# 1-Schematic_charger.net
KiCad netlist of a schematic drawn in EasyEDA
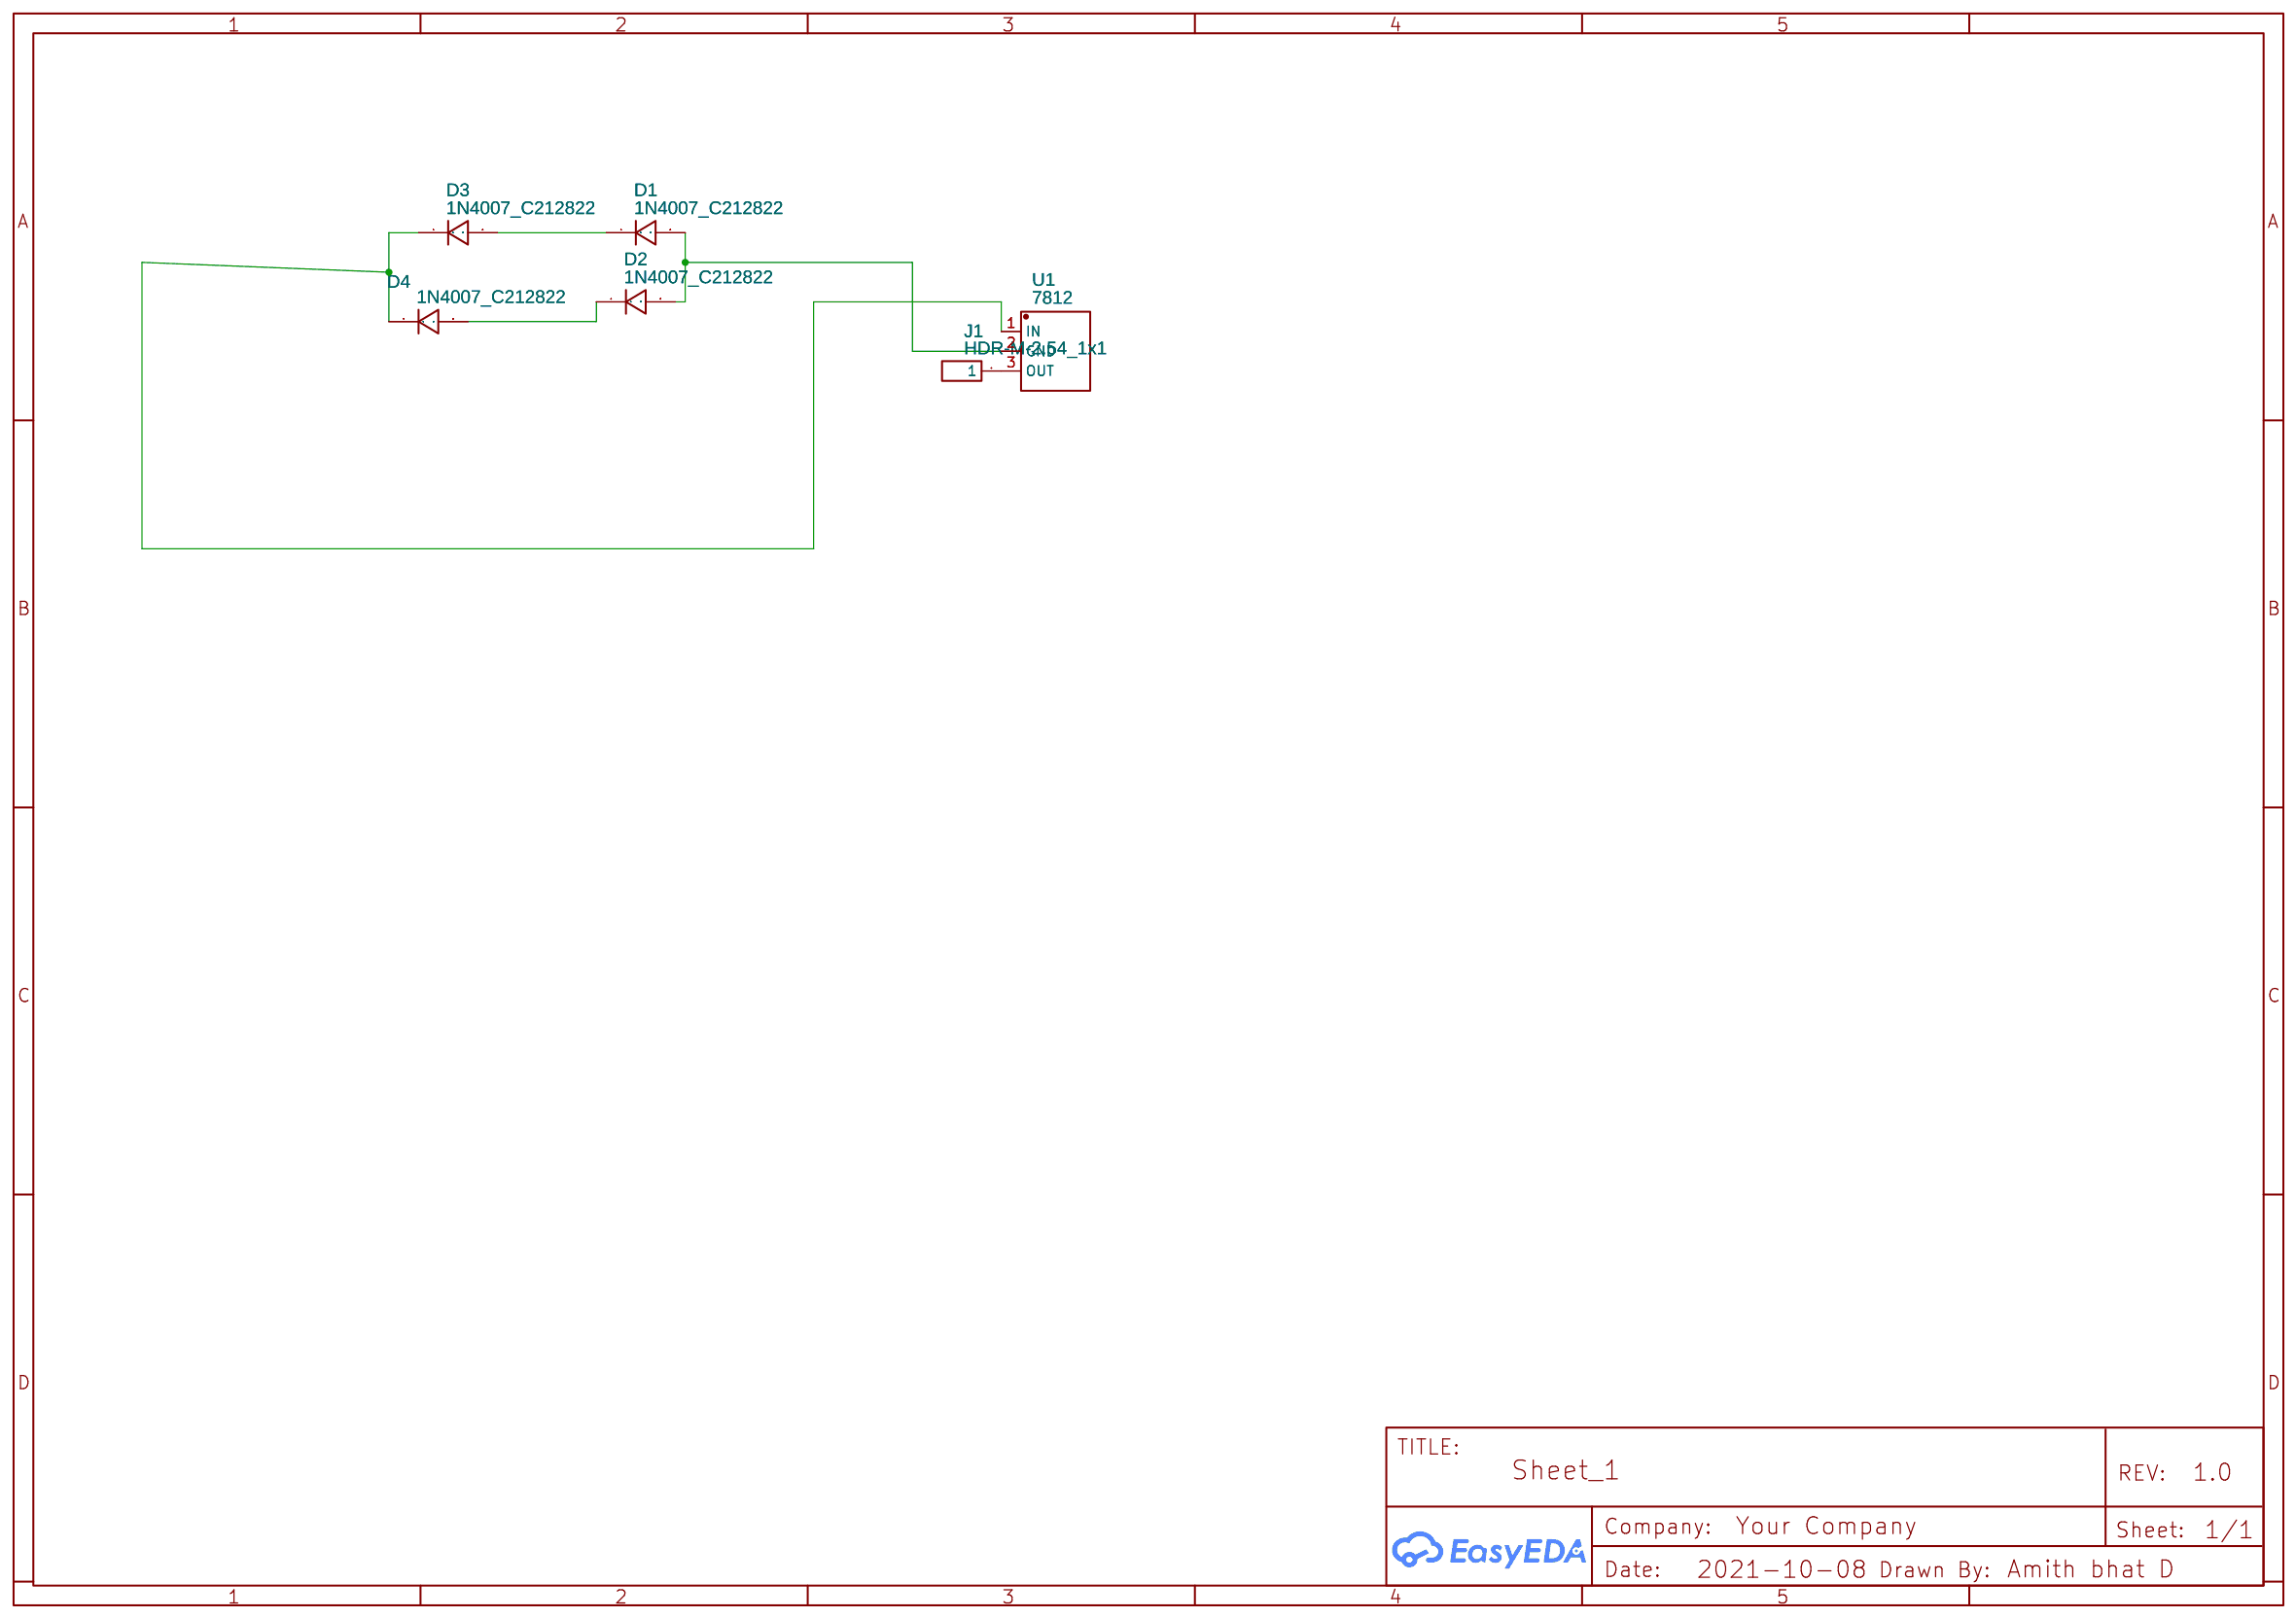
[diagram p0: schematic sheet]

(export (version "E")
  (design (tool "Eeschema 10.0.6"))
  (components
    (comp (ref "D1")
      (value "1N4007_C212822")
      (fields (field (name "BOM_Manufacturer Part") "1N4007") (field (name "BOM_Supplier Part") "C212822"))
      (libsource (lib "") (part "1N4007_C212822"))
    )
    (comp (ref "D2")
      (value "1N4007_C212822")
      (fields (field (name "BOM_Manufacturer Part") "1N4007") (field (name "BOM_Supplier Part") "C212822"))
      (libsource (lib "") (part "1N4007_C212822"))
    )
    (comp (ref "D3")
      (value "1N4007_C212822")
      (fields (field (name "BOM_Manufacturer Part") "1N4007") (field (name "BOM_Supplier Part") "C212822"))
      (libsource (lib "") (part "1N4007_C212822"))
    )
    (comp (ref "D4")
      (value "1N4007_C212822")
      (fields (field (name "BOM_Manufacturer Part") "1N4007") (field (name "BOM_Supplier Part") "C212822"))
      (libsource (lib "") (part "1N4007_C212822"))
    )
    (comp (ref "J1")
      (value "HDR-M-2.54_1x1")
      (fields (field (name "BOM_Supplier Part") "C81276"))
      (libsource (lib "") (part "HDR-M-2.54_1x1"))
    )
    (comp (ref "U1")
      (value "7812")
      (fields (field (name "BOM_Supplier Part") "C358369"))
      (libsource (lib "") (part "7812"))
    )
  )
  (nets
    (net (code "1") (name "Net-(D1-Pad1)") (class "Default")
      (node (ref "D1") (pin "1") (pinfunction "1_1") (pintype "unspecified"))
      (node (ref "D3") (pin "2") (pinfunction "2_2") (pintype "unspecified"))
    )
    (net (code "2") (name "Net-(D2-Pad1)") (class "Default")
      (node (ref "D2") (pin "1") (pinfunction "1_1") (pintype "unspecified"))
      (node (ref "D4") (pin "2") (pinfunction "2_2") (pintype "unspecified"))
    )
    (net (code "3") (name "Net-(U1-GND)") (class "Default")
      (node (ref "D1") (pin "2") (pinfunction "2_2") (pintype "unspecified"))
      (node (ref "D2") (pin "2") (pinfunction "2_2") (pintype "unspecified"))
      (node (ref "U1") (pin "2") (pinfunction "GND_2") (pintype "unspecified"))
    )
    (net (code "4") (name "Net-(U1-IN)") (class "Default")
      (node (ref "D3") (pin "1") (pinfunction "1_1") (pintype "unspecified"))
      (node (ref "D4") (pin "1") (pinfunction "1_1") (pintype "unspecified"))
      (node (ref "U1") (pin "1") (pinfunction "IN_1") (pintype "unspecified"))
    )
    (net (code "5") (name "Net-(U1-OUT)") (class "Default")
      (node (ref "J1") (pin "1") (pinfunction "1_1") (pintype "input"))
      (node (ref "U1") (pin "3") (pinfunction "OUT_3") (pintype "unspecified"))
    )
  )
)
